# USBPD.net
KiCad netlist of a schematic drawn in Altium Designer
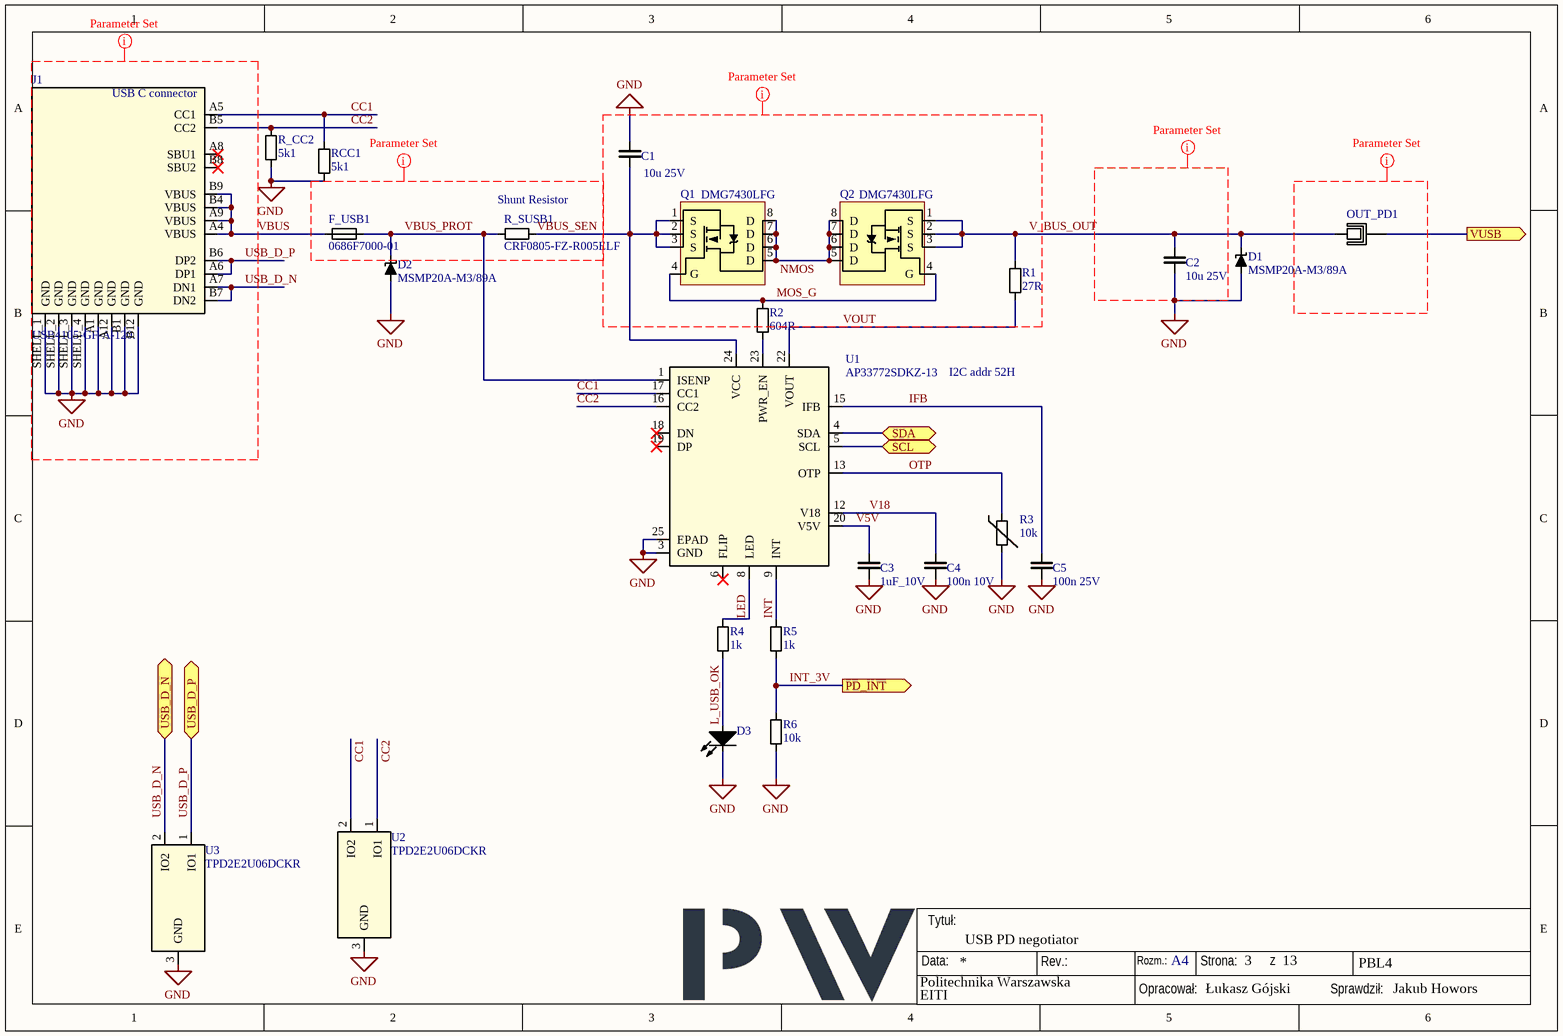
[diagram p0: USBPD.SchDoc]

(export (version "E")
  (design (tool "Eeschema 10.0.6"))
  (components
    (comp (ref "C1")
      (value "10u 25V")
      (footprint "C_0805")
      (description "Ceramic capacitor")
      (fields (field (name "VOLTAGE") "25V") (field (name "TOLERANCE") "10%"))
      (libsource (lib "Common") (part "C_10uF_25V"))
    )
    (comp (ref "C2")
      (value "10u 25V")
      (footprint "C_0805")
      (description "Ceramic capacitor")
      (fields (field (name "VOLTAGE") "25V") (field (name "TOLERANCE") "10%"))
      (libsource (lib "Common") (part "C_10uF_25V"))
    )
    (comp (ref "C3")
      (value "1uF_10V")
      (footprint "C_0603")
      (description "Ceramic capacitor")
      (fields (field (name "VOLTAGE") "10V") (field (name "TOLERANCE") "10%"))
      (libsource (lib "Common") (part "C_1uF_10V"))
    )
    (comp (ref "C4")
      (value "100n 10V")
      (footprint "C_0603")
      (description "Ceramic capacitor")
      (fields (field (name "VOLTAGE") "10V") (field (name "TOLERANCE") "10%"))
      (libsource (lib "Common") (part "C_100nF_10V"))
    )
    (comp (ref "C5")
      (value "100n 25V")
      (footprint "C_0603")
      (description "Ceramic capacitor")
      (fields (field (name "VOLTAGE") "25V") (field (name "TOLERANCE") "10%"))
      (libsource (lib "Common") (part "C_100nF_25V"))
    )
    (comp (ref "D1")
      (value "MSMP20A-M3/89A")
      (footprint "CR_0A-M389A_VIS")
      (description "22V Breakdown MSMP20A-M3/89A")
      (libsource (lib "Common") (part "TVS_22V"))
    )
    (comp (ref "D2")
      (value "MSMP20A-M3/89A")
      (footprint "CR_0A-M389A_VIS")
      (description "22V Breakdown MSMP20A-M3/89A")
      (libsource (lib "Common") (part "TVS_22V"))
    )
    (comp (ref "D3")
      (value "RED")
      (footprint "LED_0603")
      (description "LED RED 0603 3.3V")
      (libsource (lib "Common") (part "LED_0603"))
    )
    (comp (ref "F_USB1")
      (value "0686F7000-01")
      (footprint "0603_FUSE")
      (description "7A fuse 0603 package")
      (fields (field (name "MANUFACTURER") "Bel fuse Inc."))
      (libsource (lib "PowerLib") (part "F_7A"))
    )
    (comp (ref "J1")
      (value "USB4105-GF-A-120.")
      (footprint "CONN_USB4105-xx-A-xxx_GCT")
      (description "USB - C connector  16 pin, 100W, famale paraller to board")
      (fields (field (name "MANUFACTURER") "Global Connector Technology") (field (name "POWER") "100W"))
      (libsource (lib "PowerLib") (part "USB4105-GF-A-120."))
    )
    (comp (ref "OUT_PD1")
      (value "JUMPER")
      (footprint "Jumper")
      (description "Jumper on traces")
      (libsource (lib "Common") (part "Jumper x2"))
    )
    (comp (ref "Q1")
      (value "DMG7430LFG")
      (footprint "PowerDI3333-8")
      (description "DMG7430LFG, N-mosfet")
      (fields (field (name "MANUFACTURER") "Diodes Incorporated"))
      (libsource (lib "PowerLib") (part "NMOS_DMG7430LFG"))
    )
    (comp (ref "Q2")
      (value "DMG7430LFG")
      (footprint "PowerDI3333-8")
      (description "DMG7430LFG, N-mosfet")
      (fields (field (name "MANUFACTURER") "Diodes Incorporated"))
      (libsource (lib "") (part "NMOS_DMG7430LFG_1"))
    )
    (comp (ref "R1")
      (value "27R")
      (footprint "R_0603")
      (description "Resistor")
      (fields (field (name "TOLERANCE") "1%") (field (name "POWER") "100mW"))
      (libsource (lib "Common") (part "R_27R"))
    )
    (comp (ref "R2")
      (value "604R")
      (footprint "R_0603")
      (description "Resistor")
      (fields (field (name "TOLERANCE") "1%") (field (name "POWER") "100mW"))
      (libsource (lib "Common") (part "R_604R"))
    )
    (comp (ref "R3")
      (value "10k")
      (footprint "R_0603")
      (description "NTC Thermistor, 10k")
      (fields (field (name "TOLERANCE") "1%"))
      (libsource (lib "PowerLib") (part "R_NTC_10k_25C"))
    )
    (comp (ref "R4")
      (value "1k")
      (footprint "R_0603")
      (description "Resistor")
      (fields (field (name "TOLERANCE") "1%") (field (name "POWER") "100mW"))
      (libsource (lib "Common") (part "R_1k"))
    )
    (comp (ref "R5")
      (value "1k")
      (footprint "R_0603")
      (description "Resistor")
      (fields (field (name "TOLERANCE") "1%") (field (name "POWER") "100mW"))
      (libsource (lib "Common") (part "R_1k"))
    )
    (comp (ref "R6")
      (value "10k")
      (footprint "R_0603")
      (description "Resistor")
      (fields (field (name "TOLERANCE") "1%") (field (name "POWER") "100mW"))
      (libsource (lib "Common") (part "R_10k"))
    )
    (comp (ref "RCC1")
      (value "5k1")
      (footprint "R_0603")
      (description "Resistor")
      (fields (field (name "TOLERANCE") "1%") (field (name "POWER") "100mW"))
      (libsource (lib "Common") (part "R_5k1"))
    )
    (comp (ref "R_CC2")
      (value "5k1")
      (footprint "R_0603")
      (description "Resistor")
      (fields (field (name "TOLERANCE") "1%") (field (name "POWER") "100mW"))
      (libsource (lib "Common") (part "R_5k1"))
    )
    (comp (ref "R_SUSB1")
      (value "CRF0805-FZ-R005ELF")
      (footprint "R_0805")
      (description "Shunt Resistor 5mR, 0805")
      (fields (field (name "TOLERANCE") "1%") (field (name "POWER") "500mW"))
      (libsource (lib "PowerLib") (part "R_5mR"))
    )
    (comp (ref "U1")
      (value "AP33772SDKZ-13")
      (footprint "W-QFN4040-24_Type_A1_DIO-M")
      (description "USB_C PD controller")
      (fields (field (name "MANUFACTURER") "Diodes Inc"))
      (libsource (lib "PowerLib") (part "AP33772SDKZ-13"))
    )
    (comp (ref "U2")
      (value "TPD2E2U06DCKR")
      (footprint "DCK0003A-MFG")
      (fields (field (name "MANUFACTURER") "Texas Instruments"))
      (libsource (lib "PowerLib") (part "TPD2E2U06DCKR"))
    )
    (comp (ref "U3")
      (value "TPD2E2U06DCKR")
      (footprint "DCK0003A-MFG")
      (fields (field (name "MANUFACTURER") "Texas Instruments"))
      (libsource (lib "PowerLib") (part "TPD2E2U06DCKR"))
    )
  )
  (nets
    (net (code "1") (name "/CC1") (class "Default")
      (node (ref "J1") (pin "A5") (pinfunction "CC1_A5") (pintype "passive"))
      (node (ref "RCC1") (pin "2") (pinfunction "2_2") (pintype "passive"))
      (node (ref "U1") (pin "17") (pinfunction "CC1_17") (pintype "passive"))
      (node (ref "U2") (pin "2") (pinfunction "IO2_2") (pintype "passive"))
    )
    (net (code "2") (name "/CC2") (class "Default")
      (node (ref "J1") (pin "B5") (pinfunction "CC2_B5") (pintype "passive"))
      (node (ref "R_CC2") (pin "2") (pinfunction "2_2") (pintype "passive"))
      (node (ref "U1") (pin "16") (pinfunction "CC2_16") (pintype "passive"))
      (node (ref "U2") (pin "1") (pinfunction "IO1_1") (pintype "passive"))
    )
    (net (code "3") (name "/IFB") (class "Default")
      (node (ref "C5") (pin "2") (pinfunction "2_2") (pintype "passive"))
      (node (ref "U1") (pin "15") (pinfunction "IFB_15") (pintype "passive"))
    )
    (net (code "4") (name "/INT") (class "Default")
      (node (ref "R5") (pin "2") (pinfunction "2_2") (pintype "passive"))
      (node (ref "U1") (pin "9") (pinfunction "INT_9") (pintype "passive"))
    )
    (net (code "5") (name "/INT_3V") (class "Default")
      (node (ref "R5") (pin "1") (pinfunction "1_1") (pintype "passive"))
      (node (ref "R6") (pin "2") (pinfunction "2_2") (pintype "passive"))
    )
    (net (code "6") (name "/LED") (class "Default")
      (node (ref "R4") (pin "2") (pinfunction "2_2") (pintype "passive"))
      (node (ref "U1") (pin "8") (pinfunction "LED_8") (pintype "passive"))
    )
    (net (code "7") (name "/L_USB_OK") (class "Default")
      (node (ref "D3") (pin "A") (pinfunction "A_A") (pintype "passive"))
      (node (ref "R4") (pin "1") (pinfunction "1_1") (pintype "passive"))
    )
    (net (code "8") (name "/MOS_G") (class "Default")
      (node (ref "Q1") (pin "4") (pinfunction "G_4") (pintype "passive"))
      (node (ref "Q2") (pin "4") (pinfunction "G_4") (pintype "passive"))
      (node (ref "R2") (pin "2") (pinfunction "2_2") (pintype "passive"))
    )
    (net (code "9") (name "/NMOS") (class "Default")
      (node (ref "Q1") (pin "5") (pinfunction "D_5") (pintype "passive"))
      (node (ref "Q1") (pin "6") (pinfunction "D_6") (pintype "passive"))
      (node (ref "Q1") (pin "7") (pinfunction "D_7") (pintype "passive"))
      (node (ref "Q1") (pin "8") (pinfunction "D_8") (pintype "passive"))
      (node (ref "Q2") (pin "5") (pinfunction "D_5") (pintype "passive"))
      (node (ref "Q2") (pin "6") (pinfunction "D_6") (pintype "passive"))
      (node (ref "Q2") (pin "7") (pinfunction "D_7") (pintype "passive"))
      (node (ref "Q2") (pin "8") (pinfunction "D_8") (pintype "passive"))
    )
    (net (code "10") (name "/OTP") (class "Default")
      (node (ref "R3") (pin "2") (pinfunction "2_2") (pintype "passive"))
      (node (ref "U1") (pin "13") (pinfunction "OTP_13") (pintype "passive"))
    )
    (net (code "11") (name "/SCL") (class "Default")
      (node (ref "U1") (pin "5") (pinfunction "SCL_5") (pintype "passive"))
    )
    (net (code "12") (name "/SDA") (class "Default")
      (node (ref "U1") (pin "4") (pinfunction "SDA_4") (pintype "passive"))
    )
    (net (code "13") (name "/USB_D_N") (class "Default")
      (node (ref "J1") (pin "A7") (pinfunction "DN1_A7") (pintype "passive"))
      (node (ref "J1") (pin "B7") (pinfunction "DN2_B7") (pintype "passive"))
      (node (ref "U3") (pin "2") (pinfunction "IO2_2") (pintype "passive"))
    )
    (net (code "14") (name "/USB_D_P") (class "Default")
      (node (ref "J1") (pin "A6") (pinfunction "DP1_A6") (pintype "passive"))
      (node (ref "J1") (pin "B6") (pinfunction "DP2_B6") (pintype "passive"))
      (node (ref "U3") (pin "1") (pinfunction "IO1_1") (pintype "passive"))
    )
    (net (code "15") (name "/V5V") (class "Default")
      (node (ref "C3") (pin "2") (pinfunction "2_2") (pintype "passive"))
      (node (ref "U1") (pin "20") (pinfunction "V5V_20") (pintype "power_in"))
    )
    (net (code "16") (name "/V18") (class "Default")
      (node (ref "C4") (pin "2") (pinfunction "2_2") (pintype "passive"))
      (node (ref "U1") (pin "12") (pinfunction "V18_12") (pintype "power_in"))
    )
    (net (code "17") (name "/VBUS") (class "Default")
      (node (ref "F_USB1") (pin "1") (pinfunction "1_1") (pintype "passive"))
      (node (ref "J1") (pin "A4") (pinfunction "VBUS_A4") (pintype "power_in"))
      (node (ref "J1") (pin "A9") (pinfunction "VBUS_A9") (pintype "power_in"))
      (node (ref "J1") (pin "B4") (pinfunction "VBUS_B4") (pintype "power_in"))
      (node (ref "J1") (pin "B9") (pinfunction "VBUS_B9") (pintype "power_in"))
    )
    (net (code "18") (name "/VBUS_PROT") (class "Default")
      (node (ref "D2") (pin "K") (pinfunction "K_K") (pintype "passive"))
      (node (ref "F_USB1") (pin "2") (pinfunction "2_2") (pintype "passive"))
      (node (ref "R_SUSB1") (pin "1") (pinfunction "1_1") (pintype "passive"))
      (node (ref "U1") (pin "1") (pinfunction "ISENP_1") (pintype "passive"))
    )
    (net (code "19") (name "/VBUS_SEN") (class "Default")
      (node (ref "C1") (pin "1") (pinfunction "1_1") (pintype "passive"))
      (node (ref "Q1") (pin "1") (pinfunction "S_1") (pintype "passive"))
      (node (ref "Q1") (pin "2") (pinfunction "S_2") (pintype "passive"))
      (node (ref "Q1") (pin "3") (pinfunction "S_3") (pintype "passive"))
      (node (ref "R_SUSB1") (pin "2") (pinfunction "2_2") (pintype "passive"))
      (node (ref "U1") (pin "24") (pinfunction "VCC_24") (pintype "passive"))
    )
    (net (code "20") (name "/VOUT") (class "Default")
      (node (ref "R1") (pin "1") (pinfunction "1_1") (pintype "passive"))
      (node (ref "U1") (pin "22") (pinfunction "VOUT_22") (pintype "passive"))
    )
    (net (code "21") (name "/VUSB") (class "Default")
      (node (ref "OUT_PD1") (pin "2") (pinfunction "2_2") (pintype "passive"))
    )
    (net (code "22") (name "/V_BUS_OUT") (class "Default")
      (node (ref "C2") (pin "2") (pinfunction "2_2") (pintype "passive"))
      (node (ref "D1") (pin "K") (pinfunction "K_K") (pintype "passive"))
      (node (ref "OUT_PD1") (pin "1") (pinfunction "1_1") (pintype "passive"))
      (node (ref "Q2") (pin "1") (pinfunction "S_1") (pintype "passive"))
      (node (ref "Q2") (pin "2") (pinfunction "S_2") (pintype "passive"))
      (node (ref "Q2") (pin "3") (pinfunction "S_3") (pintype "passive"))
      (node (ref "R1") (pin "2") (pinfunction "2_2") (pintype "passive"))
    )
    (net (code "23") (name "GND") (class "Default")
      (node (ref "C1") (pin "2") (pinfunction "2_2") (pintype "passive"))
      (node (ref "C2") (pin "1") (pinfunction "1_1") (pintype "passive"))
      (node (ref "C3") (pin "1") (pinfunction "1_1") (pintype "passive"))
      (node (ref "C4") (pin "1") (pinfunction "1_1") (pintype "passive"))
      (node (ref "C5") (pin "1") (pinfunction "1_1") (pintype "passive"))
      (node (ref "D1") (pin "A") (pinfunction "A_A") (pintype "passive"))
      (node (ref "D2") (pin "A") (pinfunction "A_A") (pintype "passive"))
      (node (ref "D3") (pin "K") (pinfunction "K_K") (pintype "passive"))
      (node (ref "J1") (pin "A1") (pinfunction "GND_A1") (pintype "power_in"))
      (node (ref "J1") (pin "A12") (pinfunction "GND_A12") (pintype "power_in"))
      (node (ref "J1") (pin "B1") (pinfunction "GND_B1") (pintype "power_in"))
      (node (ref "J1") (pin "B12") (pinfunction "GND_B12") (pintype "power_in"))
      (node (ref "J1") (pin "SHELL_1") (pinfunction "GND_SHELL_1") (pintype "power_in"))
      (node (ref "J1") (pin "SHELL_2") (pinfunction "GND_SHELL_2") (pintype "power_in"))
      (node (ref "J1") (pin "SHELL_3") (pinfunction "GND_SHELL_3") (pintype "power_in"))
      (node (ref "J1") (pin "SHELL_4") (pinfunction "GND_SHELL_4") (pintype "power_in"))
      (node (ref "R3") (pin "1") (pinfunction "1_1") (pintype "passive"))
      (node (ref "R6") (pin "1") (pinfunction "1_1") (pintype "passive"))
      (node (ref "RCC1") (pin "1") (pinfunction "1_1") (pintype "passive"))
      (node (ref "R_CC2") (pin "1") (pinfunction "1_1") (pintype "passive"))
      (node (ref "U1") (pin "25") (pinfunction "EPAD_25") (pintype "power_in"))
      (node (ref "U1") (pin "3") (pinfunction "GND_3") (pintype "power_in"))
      (node (ref "U2") (pin "3") (pinfunction "GND_3") (pintype "power_in"))
      (node (ref "U3") (pin "3") (pinfunction "GND_3") (pintype "power_in"))
    )
    (net (code "24") (name "Net-(U1-PWR_EN)") (class "Default")
      (node (ref "R2") (pin "1") (pinfunction "1_1") (pintype "passive"))
      (node (ref "U1") (pin "23") (pinfunction "PWR_EN_23") (pintype "passive"))
    )
    (net (code "25") (name "unconnected-(J1-SBU1-PadA8)") (class "Default")
      (node (ref "J1") (pin "A8") (pinfunction "SBU1_A8") (pintype "passive+no_connect"))
    )
    (net (code "26") (name "unconnected-(J1-SBU2-PadB8)") (class "Default")
      (node (ref "J1") (pin "B8") (pinfunction "SBU2_B8") (pintype "passive+no_connect"))
    )
    (net (code "27") (name "unconnected-(U1-DN-Pad18)") (class "Default")
      (node (ref "U1") (pin "18") (pinfunction "DN_18") (pintype "passive+no_connect"))
    )
    (net (code "28") (name "unconnected-(U1-DP-Pad19)") (class "Default")
      (node (ref "U1") (pin "19") (pinfunction "DP_19") (pintype "passive+no_connect"))
    )
    (net (code "29") (name "unconnected-(U1-FLIP-Pad6)") (class "Default")
      (node (ref "U1") (pin "6") (pinfunction "FLIP_6") (pintype "passive+no_connect"))
    )
    (net (code "30") (name "unconnected-(U1-NC-Pad2)") (class "Default")
      (node (ref "U1") (pin "2") (pinfunction "NC_2") (pintype "passive"))
    )
    (net (code "31") (name "unconnected-(U1-NC-Pad7)") (class "Default")
      (node (ref "U1") (pin "7") (pinfunction "NC_7") (pintype "passive"))
    )
    (net (code "32") (name "unconnected-(U1-NC-Pad10)") (class "Default")
      (node (ref "U1") (pin "10") (pinfunction "NC_10") (pintype "passive"))
    )
    (net (code "33") (name "unconnected-(U1-NC-Pad11)") (class "Default")
      (node (ref "U1") (pin "11") (pinfunction "NC_11") (pintype "passive"))
    )
    (net (code "34") (name "unconnected-(U1-NC-Pad14)") (class "Default")
      (node (ref "U1") (pin "14") (pinfunction "NC_14") (pintype "passive"))
    )
    (net (code "35") (name "unconnected-(U1-NC-Pad21)") (class "Default")
      (node (ref "U1") (pin "21") (pinfunction "NC_21") (pintype "passive"))
    )
  )
)
